# PowerSupply.net
KiCad netlist of a schematic drawn in Altium Designer
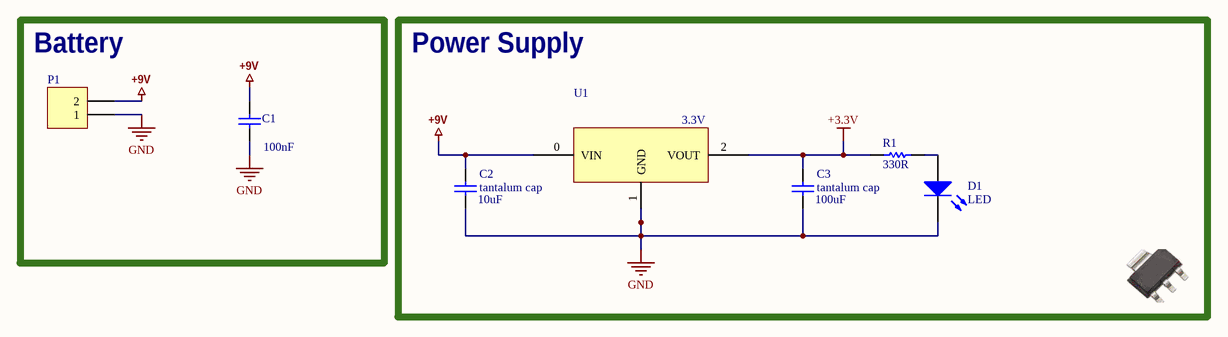
[diagram p0: PowerSupply.SchDoc]

(export (version "E")
  (design (tool "Eeschema 10.0.6"))
  (components
    (comp (ref "C1")
      (value "100nF")
      (footprint "C1206")
      (description "Capacitor (Semiconductor SIM Model)")
      (fields (field (name "PUBLISHER") "Altium Limited"))
      (libsource (lib "Miscellaneous Devices") (part "Cap Semi"))
    )
    (comp (ref "C2")
      (value "tantalum cap")
      (footprint "C1206tancap")
      (description "Capacitor (Semiconductor SIM Model)")
      (fields (field (name "ALTIUM_VALUE") "10uF") (field (name "PUBLISHER") "Altium Limited"))
      (libsource (lib "smartmcu_udemy") (part "Cap Semi_5"))
    )
    (comp (ref "C3")
      (value "tantalum cap")
      (footprint "C1206tancap")
      (description "Capacitor (Semiconductor SIM Model)")
      (fields (field (name "ALTIUM_VALUE") "100uF") (field (name "PUBLISHER") "Altium Limited"))
      (libsource (lib "smartmcu_udemy") (part "Cap Semi_5"))
    )
    (comp (ref "D1")
      (value "LED")
      (footprint "MY_LED_0805")
      (description "Typical INFRARED GaAs LED")
      (fields (field (name "ASID PART NUMBER") "LED-AS"))
      (libsource (lib "Mylib+Rev+4") (part "LED"))
    )
    (comp (ref "P1")
      (value "~")
      (footprint "HDR1X2H")
      (description "Header, 2-Pin, Right Angle")
      (fields (field (name "PUBLISHER") "Altium Limited"))
      (libsource (lib "smartmcu") (part "Header 2H"))
    )
    (comp (ref "R1")
      (value "330R")
      (footprint "MY_0805")
      (description "Standard resistor")
      (fields (field (name "ASID PART NUMBER") "Res-AS"))
      (libsource (lib "Mylib+Rev+4") (part "Res"))
    )
    (comp (ref "U1")
      (value "~")
      (footprint "4-Pin SOT")
      (fields (field (name "OUTPUT VOLTAGE") "3.3V"))
      (libsource (lib "smartmcu_udemy") (part "lm1117"))
    )
  )
  (nets
    (net (code "1") (name "+3.3V") (class "Default")
      (node (ref "C3") (pin "2") (pinfunction "2_2") (pintype "passive"))
      (node (ref "R1") (pin "1") (pinfunction "1_1") (pintype "passive"))
      (node (ref "U1") (pin "2") (pinfunction "VOUT_2") (pintype "passive"))
    )
    (net (code "2") (name "+9V") (class "Default")
      (node (ref "C1") (pin "2") (pinfunction "2_2") (pintype "passive"))
      (node (ref "C2") (pin "2") (pinfunction "2_2") (pintype "passive"))
      (node (ref "P1") (pin "2") (pinfunction "2_2") (pintype "passive"))
      (node (ref "U1") (pin "0") (pinfunction "VIN_0") (pintype "passive"))
    )
    (net (code "3") (name "GND") (class "Default")
      (node (ref "C1") (pin "1") (pinfunction "1_1") (pintype "passive"))
      (node (ref "C2") (pin "1") (pinfunction "1_1") (pintype "passive"))
      (node (ref "C3") (pin "1") (pinfunction "1_1") (pintype "passive"))
      (node (ref "D1") (pin "K") (pinfunction "K_K") (pintype "passive"))
      (node (ref "P1") (pin "1") (pinfunction "1_1") (pintype "passive"))
      (node (ref "U1") (pin "1") (pinfunction "GND_1") (pintype "passive"))
    )
    (net (code "4") (name "Net-(D1-PadA)") (class "Default")
      (node (ref "D1") (pin "A") (pinfunction "A_A") (pintype "passive"))
      (node (ref "R1") (pin "2") (pinfunction "2_2") (pintype "passive"))
    )
  )
)
